# L298.net
KiCad netlist of a schematic drawn in Altium Designer
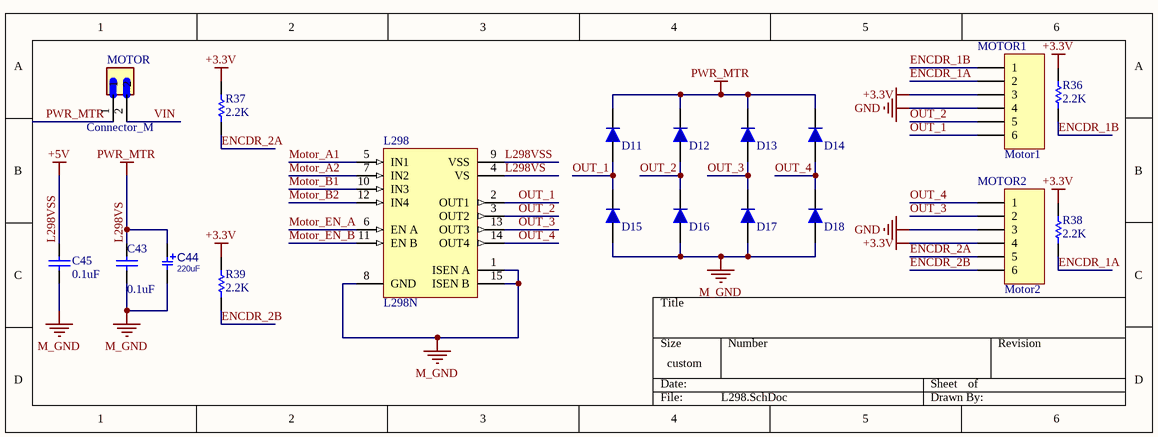
[diagram p0: L298.SchDoc]

(export (version "E")
  (design (tool "Eeschema 10.0.6"))
  (components
    (comp (ref "C43")
      (value "0.1uF")
      (footprint "CAPC3413X12N")
      (description "CAP 0805")
      (fields (field (name "DESIGNER") "Abbas Basereh"))
      (libsource (lib "Altium") (part "CAP SMD 0805"))
    )
    (comp (ref "C44")
      (value "220uF")
      (footprint "C_EL_6_6")
      (description "CAP, THD, ELEC,")
      (fields (field (name "MANF_P#") "MANF_PART#") (field (name "MANF") "MANF"))
      (libsource (lib "Passive") (part "CAP_SMD_EL"))
    )
    (comp (ref "C45")
      (value "0.1uF")
      (footprint "CAPC3413X12N")
      (description "CAP 0805")
      (fields (field (name "DESIGNER") "Abbas Basereh"))
      (libsource (lib "Altium") (part "CAP SMD 0805"))
    )
    (comp (ref "D11")
      (value "1n4007")
      (footprint "DIOM4629X24N")
      (description "Standard Rectifiers")
      (fields (field (name "MANUFACTURER") "DC COMPONENTS") (field (name "DESIGNER") "Abbas Basereh"))
      (libsource (lib "Altium") (part "1n4007 SMD M7"))
    )
    (comp (ref "D12")
      (value "1n4007")
      (footprint "DIOM4629X24N")
      (description "Standard Rectifiers")
      (fields (field (name "MANUFACTURER") "DC COMPONENTS") (field (name "DESIGNER") "Abbas Basereh"))
      (libsource (lib "Altium") (part "1n4007 SMD M7"))
    )
    (comp (ref "D13")
      (value "1n4007")
      (footprint "DIOM4629X24N")
      (description "Standard Rectifiers")
      (fields (field (name "MANUFACTURER") "DC COMPONENTS") (field (name "DESIGNER") "Abbas Basereh"))
      (libsource (lib "Altium") (part "1n4007 SMD M7"))
    )
    (comp (ref "D14")
      (value "1n4007")
      (footprint "DIOM4629X24N")
      (description "Standard Rectifiers")
      (fields (field (name "MANUFACTURER") "DC COMPONENTS") (field (name "DESIGNER") "Abbas Basereh"))
      (libsource (lib "Altium") (part "1n4007 SMD M7"))
    )
    (comp (ref "D15")
      (value "1n4007")
      (footprint "DIOM4629X24N")
      (description "Standard Rectifiers")
      (fields (field (name "MANUFACTURER") "DC COMPONENTS") (field (name "DESIGNER") "Abbas Basereh"))
      (libsource (lib "Altium") (part "1n4007 SMD M7"))
    )
    (comp (ref "D16")
      (value "1n4007")
      (footprint "DIOM4629X24N")
      (description "Standard Rectifiers")
      (fields (field (name "MANUFACTURER") "DC COMPONENTS") (field (name "DESIGNER") "Abbas Basereh"))
      (libsource (lib "Altium") (part "1n4007 SMD M7"))
    )
    (comp (ref "D17")
      (value "1n4007")
      (footprint "DIOM4629X24N")
      (description "Standard Rectifiers")
      (fields (field (name "MANUFACTURER") "DC COMPONENTS") (field (name "DESIGNER") "Abbas Basereh"))
      (libsource (lib "Altium") (part "1n4007 SMD M7"))
    )
    (comp (ref "D18")
      (value "1n4007")
      (footprint "DIOM4629X24N")
      (description "Standard Rectifiers")
      (fields (field (name "MANUFACTURER") "DC COMPONENTS") (field (name "DESIGNER") "Abbas Basereh"))
      (libsource (lib "Altium") (part "1n4007 SMD M7"))
    )
    (comp (ref "L298")
      (value "L298N")
      (footprint "Multiwatt15H")
      (description "Dual Full Bridge Driver")
      (fields (field (name "PUBLISHER") "Altium Limited"))
      (libsource (lib "Altium") (part "L298N"))
    )
    (comp (ref "MOTOR")
      (value "Connector_M")
      (footprint "JST_B2P-VH(LF)(SN)")
      (description "Connector Header Through Hole 2 position 0.156 (3.96mm)")
      (fields (field (name "MP") "B2P-VH(LF)(SN)") (field (name "MF") "JST Sales"))
      (libsource (lib "B2P-VH_LF__SN_") (part "B2P-VH(LF)(SN)"))
    )
    (comp (ref "MOTOR1")
      (value "Motor1")
      (footprint "MO-Header 6")
      (description "Header, 6-Pin")
      (fields (field (name "PUBLISHER") "Altium Limited"))
      (libsource (lib "Altium") (part "Header 6"))
    )
    (comp (ref "MOTOR2")
      (value "Motor2")
      (footprint "MO-Header 6")
      (description "Header, 6-Pin")
      (fields (field (name "PUBLISHER") "Altium Limited"))
      (libsource (lib "Altium") (part "Header 6"))
    )
    (comp (ref "R36")
      (value "2.2K")
      (footprint "RESC3413X04N")
      (description "RES 0805")
      (fields (field (name "DESIGNER") "Abbas Basereh"))
      (libsource (lib "Altium") (part "RES 0805 0.125W"))
    )
    (comp (ref "R37")
      (value "2.2K")
      (footprint "RESC3413X04N")
      (description "RES 0805")
      (fields (field (name "DESIGNER") "Abbas Basereh"))
      (libsource (lib "Altium") (part "RES 0805 0.125W"))
    )
    (comp (ref "R38")
      (value "2.2K")
      (footprint "RESC3413X04N")
      (description "RES 0805")
      (fields (field (name "DESIGNER") "Abbas Basereh"))
      (libsource (lib "Altium") (part "RES 0805 0.125W"))
    )
    (comp (ref "R39")
      (value "2.2K")
      (footprint "RESC3413X04N")
      (description "RES 0805")
      (fields (field (name "DESIGNER") "Abbas Basereh"))
      (libsource (lib "Altium") (part "RES 0805 0.125W"))
    )
  )
  (nets
    (net (code "1") (name "+3.3V") (class "Default")
      (node (ref "MOTOR1") (pin "3") (pinfunction "3_3") (pintype "passive"))
      (node (ref "MOTOR2") (pin "4") (pinfunction "4_4") (pintype "passive"))
      (node (ref "R36") (pin "1") (pinfunction "1_1") (pintype "passive"))
      (node (ref "R37") (pin "1") (pinfunction "1_1") (pintype "passive"))
      (node (ref "R38") (pin "1") (pinfunction "1_1") (pintype "passive"))
      (node (ref "R39") (pin "1") (pinfunction "1_1") (pintype "passive"))
    )
    (net (code "2") (name "+5V") (class "Default")
      (node (ref "C45") (pin "2") (pinfunction "2_2") (pintype "passive"))
      (node (ref "L298") (pin "9") (pinfunction "VSS_9") (pintype "power_in"))
    )
    (net (code "3") (name "/ENCDR_1A") (class "Default")
      (node (ref "MOTOR1") (pin "2") (pinfunction "2_2") (pintype "passive"))
      (node (ref "R38") (pin "2") (pinfunction "2_2") (pintype "passive"))
    )
    (net (code "4") (name "/ENCDR_1B") (class "Default")
      (node (ref "MOTOR1") (pin "1") (pinfunction "1_1") (pintype "passive"))
      (node (ref "R36") (pin "2") (pinfunction "2_2") (pintype "passive"))
    )
    (net (code "5") (name "/ENCDR_2A") (class "Default")
      (node (ref "MOTOR2") (pin "5") (pinfunction "5_5") (pintype "passive"))
      (node (ref "R37") (pin "2") (pinfunction "2_2") (pintype "passive"))
    )
    (net (code "6") (name "/ENCDR_2B") (class "Default")
      (node (ref "MOTOR2") (pin "6") (pinfunction "6_6") (pintype "passive"))
      (node (ref "R39") (pin "2") (pinfunction "2_2") (pintype "passive"))
    )
    (net (code "7") (name "/Motor_A1") (class "Default")
      (node (ref "L298") (pin "5") (pinfunction "IN1_5") (pintype "input"))
    )
    (net (code "8") (name "/Motor_A2") (class "Default")
      (node (ref "L298") (pin "7") (pinfunction "IN2_7") (pintype "input"))
    )
    (net (code "9") (name "/Motor_B1") (class "Default")
      (node (ref "L298") (pin "10") (pinfunction "IN3_10") (pintype "input"))
    )
    (net (code "10") (name "/Motor_B2") (class "Default")
      (node (ref "L298") (pin "12") (pinfunction "IN4_12") (pintype "input"))
    )
    (net (code "11") (name "/Motor_EN_A") (class "Default")
      (node (ref "L298") (pin "6") (pinfunction "EN_A_6") (pintype "input"))
    )
    (net (code "12") (name "/Motor_EN_B") (class "Default")
      (node (ref "L298") (pin "11") (pinfunction "EN_B_11") (pintype "input"))
    )
    (net (code "13") (name "/OUT_1") (class "Default")
      (node (ref "D11") (pin "1") (pintype "passive"))
      (node (ref "D15") (pin "2") (pintype "passive"))
      (node (ref "L298") (pin "2") (pinfunction "OUT1_2") (pintype "output"))
      (node (ref "MOTOR1") (pin "6") (pinfunction "6_6") (pintype "passive"))
    )
    (net (code "14") (name "/OUT_2") (class "Default")
      (node (ref "D12") (pin "1") (pintype "passive"))
      (node (ref "D16") (pin "2") (pintype "passive"))
      (node (ref "L298") (pin "3") (pinfunction "OUT2_3") (pintype "output"))
      (node (ref "MOTOR1") (pin "5") (pinfunction "5_5") (pintype "passive"))
    )
    (net (code "15") (name "/OUT_3") (class "Default")
      (node (ref "D13") (pin "1") (pintype "passive"))
      (node (ref "D17") (pin "2") (pintype "passive"))
      (node (ref "L298") (pin "13") (pinfunction "OUT3_13") (pintype "output"))
      (node (ref "MOTOR2") (pin "2") (pinfunction "2_2") (pintype "passive"))
    )
    (net (code "16") (name "/OUT_4") (class "Default")
      (node (ref "D14") (pin "1") (pintype "passive"))
      (node (ref "D18") (pin "2") (pintype "passive"))
      (node (ref "L298") (pin "14") (pinfunction "OUT4_14") (pintype "output"))
      (node (ref "MOTOR2") (pin "1") (pinfunction "1_1") (pintype "passive"))
    )
    (net (code "17") (name "/VIN") (class "Default")
      (node (ref "MOTOR") (pin "2") (pinfunction "2_2") (pintype "passive"))
    )
    (net (code "18") (name "GND") (class "Default")
      (node (ref "MOTOR1") (pin "4") (pinfunction "4_4") (pintype "passive"))
      (node (ref "MOTOR2") (pin "3") (pinfunction "3_3") (pintype "passive"))
    )
    (net (code "19") (name "M_GND") (class "Default")
      (node (ref "C43") (pin "1") (pinfunction "1_1") (pintype "passive"))
      (node (ref "C44") (pin "2") (pinfunction "2_2") (pintype "passive"))
      (node (ref "C45") (pin "1") (pinfunction "1_1") (pintype "passive"))
      (node (ref "D15") (pin "1") (pintype "passive"))
      (node (ref "D16") (pin "1") (pintype "passive"))
      (node (ref "D17") (pin "1") (pintype "passive"))
      (node (ref "D18") (pin "1") (pintype "passive"))
      (node (ref "L298") (pin "1") (pinfunction "ISEN_A_1") (pintype "passive"))
      (node (ref "L298") (pin "15") (pinfunction "ISEN_B_15") (pintype "passive"))
      (node (ref "L298") (pin "8") (pinfunction "GND_8") (pintype "power_in"))
    )
    (net (code "20") (name "PWR_MTR") (class "Default")
      (node (ref "C43") (pin "2") (pinfunction "2_2") (pintype "passive"))
      (node (ref "C44") (pin "1") (pinfunction "1_1") (pintype "passive"))
      (node (ref "D11") (pin "2") (pintype "passive"))
      (node (ref "D12") (pin "2") (pintype "passive"))
      (node (ref "D13") (pin "2") (pintype "passive"))
      (node (ref "D14") (pin "2") (pintype "passive"))
      (node (ref "L298") (pin "4") (pinfunction "VS_4") (pintype "power_in"))
      (node (ref "MOTOR") (pin "1") (pinfunction "1_1") (pintype "passive"))
    )
  )
)
